# Mega_Shield.net
KiCad netlist of a schematic drawn in EAGLE
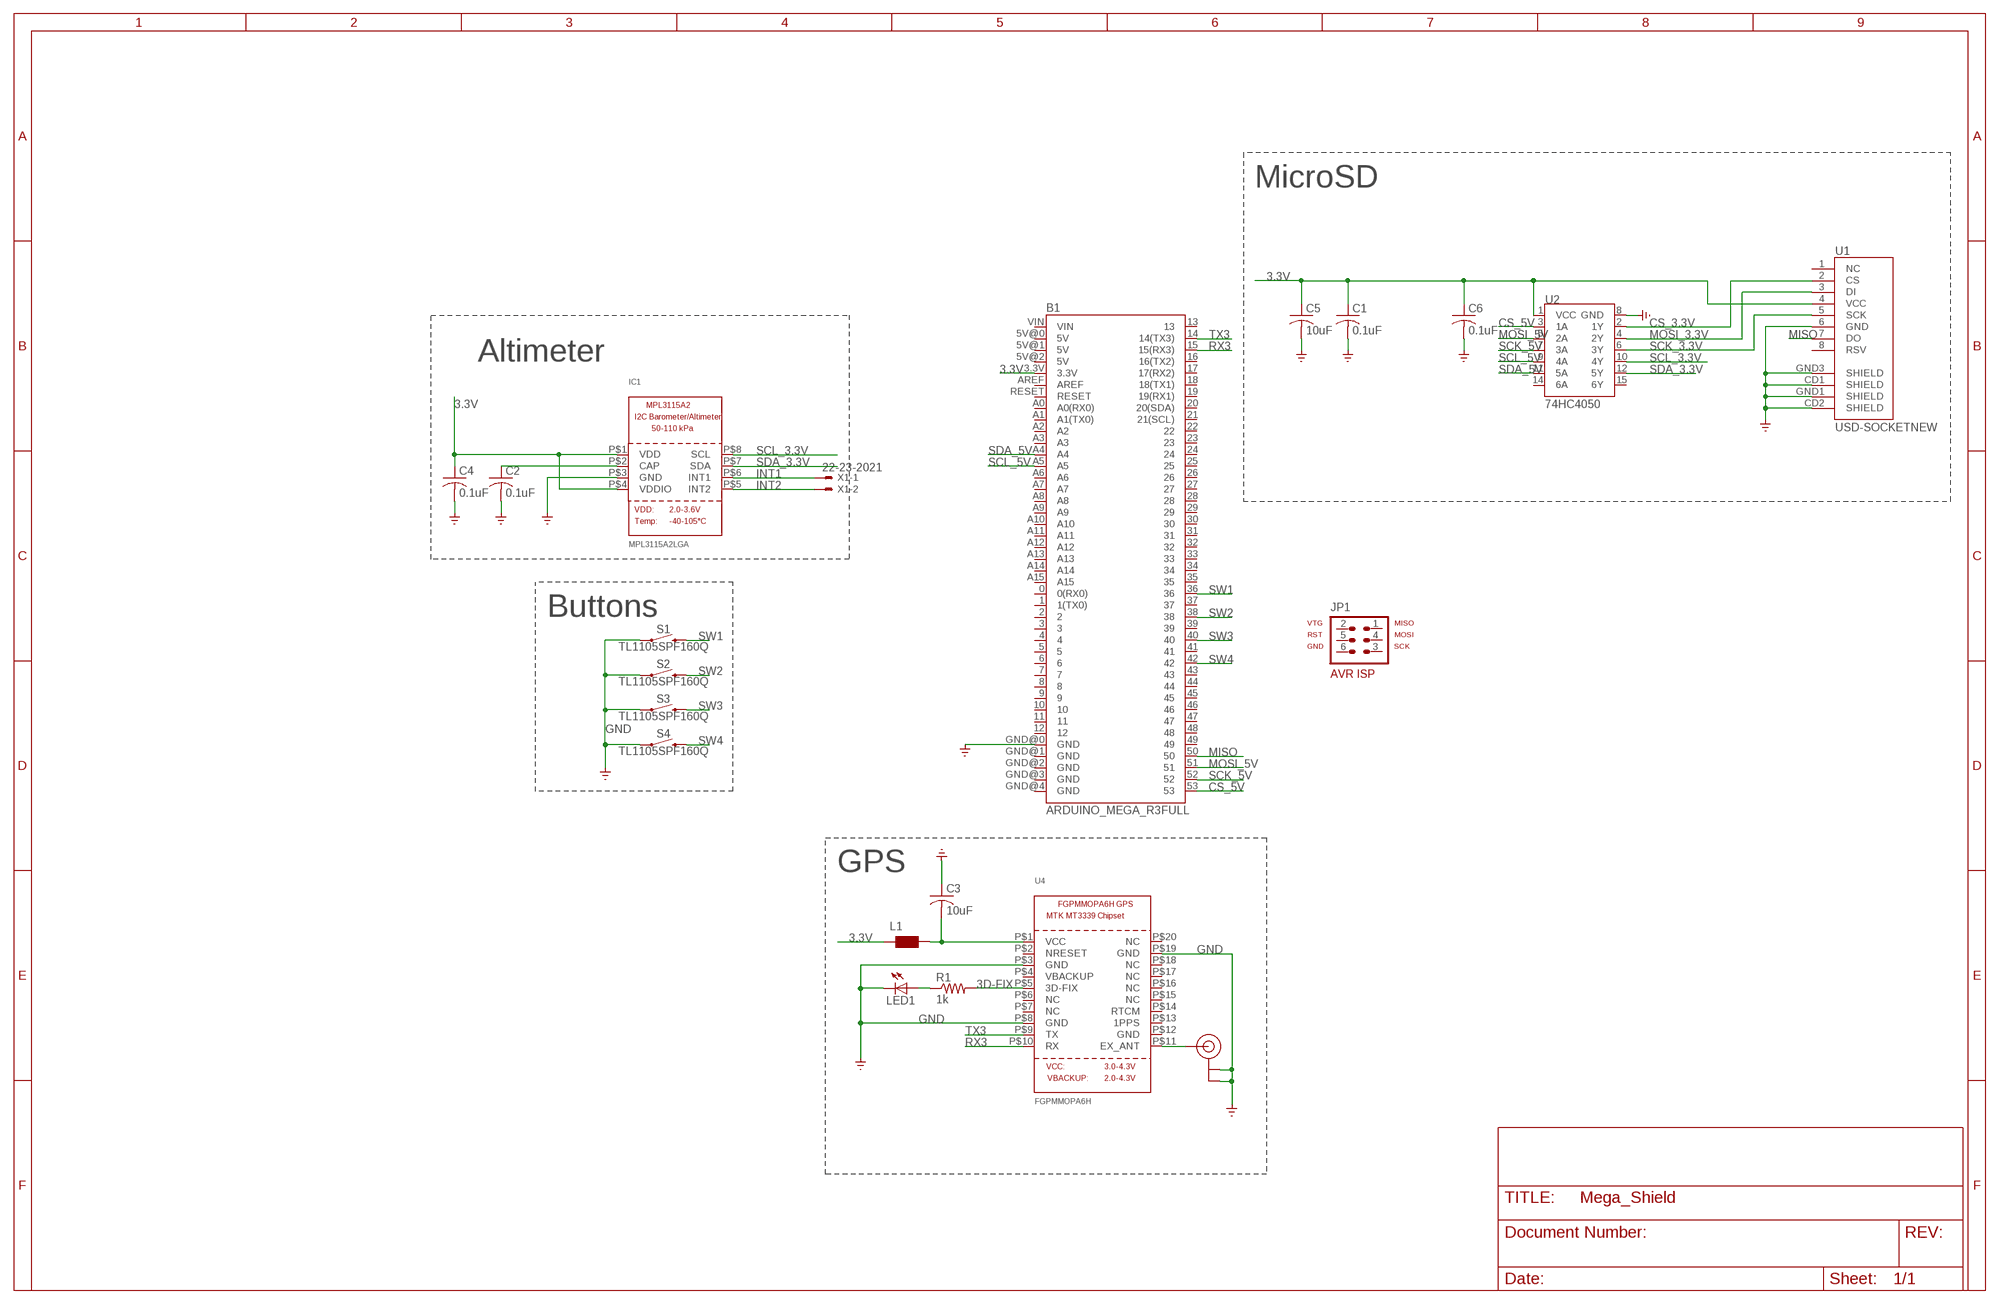
[diagram p0: schematic, sheet 1]

(export (version "E")
  (design (tool "Eeschema 10.0.6"))
  (components
    (comp (ref "B1")
      (value "ARDUINO_MEGA_R3FULL")
      (footprint "eagle-import:ARDUINO_MEGA")
      (libsource (lib "eagle-import") (part "ARDUINO_MEGA_R3FULL"))
    )
    (comp (ref "C1")
      (value "0.1uF")
      (footprint "eagle-import:C1206")
      (libsource (lib "eagle-import") (part "C-USC1206"))
    )
    (comp (ref "C2")
      (value "0.1uF")
      (footprint "eagle-import:C1206")
      (libsource (lib "eagle-import") (part "C-USC1206"))
    )
    (comp (ref "C3")
      (value "10uF")
      (footprint "eagle-import:C1206")
      (libsource (lib "eagle-import") (part "C-USC1206"))
    )
    (comp (ref "C4")
      (value "0.1uF")
      (footprint "eagle-import:C1206")
      (libsource (lib "eagle-import") (part "C-USC1206"))
    )
    (comp (ref "C5")
      (value "10uF")
      (footprint "eagle-import:C1206")
      (libsource (lib "eagle-import") (part "C-USC1206"))
    )
    (comp (ref "C6")
      (value "0.1uF")
      (footprint "eagle-import:C1206")
      (libsource (lib "eagle-import") (part "C-USC1206"))
    )
    (comp (ref "IC1")
      (value "MPL3115A2LGA")
      (footprint "eagle-import:LGA8")
      (libsource (lib "eagle-import") (part "MPL3115A2LGA"))
    )
    (comp (ref "JP1")
      (value "AVR-ISP-6")
      (footprint "eagle-import:AVR-ISP-6")
      (libsource (lib "eagle-import") (part "AVR-ISP-6"))
    )
    (comp (ref "L1")
      (value "WE-CBF_1206")
      (footprint "eagle-import:1206")
      (libsource (lib "eagle-import") (part "WE-CBF_1206"))
    )
    (comp (ref "LED1")
      (value "LEDSMT1206")
      (footprint "eagle-import:1206")
      (libsource (lib "eagle-import") (part "LEDSMT1206"))
    )
    (comp (ref "R1")
      (value "1k")
      (footprint "eagle-import:R1206")
      (libsource (lib "eagle-import") (part "R-US_R1206"))
    )
    (comp (ref "S1")
      (value "TL1105SPF160Q")
      (footprint "eagle-import:TACTILE_SWITCH_PTH_6.0MM")
      (libsource (lib "eagle-import") (part "MOMENTARY-SWITCH-SPST-PTH-6.0MM"))
    )
    (comp (ref "S2")
      (value "TL1105SPF160Q")
      (footprint "eagle-import:TACTILE_SWITCH_PTH_6.0MM")
      (libsource (lib "eagle-import") (part "MOMENTARY-SWITCH-SPST-PTH-6.0MM"))
    )
    (comp (ref "S3")
      (value "TL1105SPF160Q")
      (footprint "eagle-import:TACTILE_SWITCH_PTH_6.0MM")
      (libsource (lib "eagle-import") (part "MOMENTARY-SWITCH-SPST-PTH-6.0MM"))
    )
    (comp (ref "S4")
      (value "TL1105SPF160Q")
      (footprint "eagle-import:TACTILE_SWITCH_PTH_6.0MM")
      (libsource (lib "eagle-import") (part "MOMENTARY-SWITCH-SPST-PTH-6.0MM"))
    )
    (comp (ref "U$20")
      (value "U.FL")
      (footprint "eagle-import:U.FL")
      (libsource (lib "eagle-import") (part "U.FL"))
    )
    (comp (ref "U1")
      (value "USD-SOCKETNEW")
      (footprint "eagle-import:MICRO-SD-SOCKET-PP")
      (libsource (lib "eagle-import") (part "USD-SOCKETNEW"))
    )
    (comp (ref "U2")
      (value "74HC4050")
      (footprint "eagle-import:SO16")
      (libsource (lib "eagle-import") (part "HEX_CONVERTER"))
    )
    (comp (ref "U4")
      (value "FGPMMOPA6H")
      (footprint "eagle-import:FGPMMOPA6H")
      (libsource (lib "eagle-import") (part "GPS_FGPMMOPA6H"))
    )
    (comp (ref "X1")
      (value "22-23-2021")
      (footprint "eagle-import:22-23-2021")
      (fields (field (name "MF") "MOLEX"))
      (libsource (lib "eagle-import") (part "22-23-2021"))
    )
  )
  (nets
    (net (code "1") (name "/3.3V") (class "Default")
      (node (ref "B1") (pin "3.3V") (pinfunction "3.3V_3.3V") (pintype "bidirectional"))
      (node (ref "C1") (pin "1") (pinfunction "1_1") (pintype "passive"))
      (node (ref "C4") (pin "1") (pinfunction "1_1") (pintype "passive"))
      (node (ref "C5") (pin "1") (pinfunction "1_1") (pintype "passive"))
      (node (ref "C6") (pin "1") (pinfunction "1_1") (pintype "passive"))
      (node (ref "IC1") (pin "P$1") (pinfunction "VDD_P$1") (pintype "power_in"))
      (node (ref "IC1") (pin "P$4") (pinfunction "VDDIO_P$4") (pintype "power_in"))
      (node (ref "L1") (pin "1") (pinfunction "1_1") (pintype "passive"))
      (node (ref "U1") (pin "4") (pinfunction "VCC_4") (pintype "bidirectional"))
      (node (ref "U2") (pin "1") (pinfunction "VCC_1") (pintype "bidirectional"))
    )
    (net (code "2") (name "/3D-FIX") (class "Default")
      (node (ref "R1") (pin "2") (pinfunction "2_2") (pintype "passive"))
      (node (ref "U4") (pin "P$5") (pinfunction "3D-FIX_P$5") (pintype "bidirectional"))
    )
    (net (code "3") (name "/CS_3.3V") (class "Default")
      (node (ref "U1") (pin "2") (pinfunction "CS_2") (pintype "bidirectional"))
      (node (ref "U2") (pin "2") (pinfunction "1Y_2") (pintype "bidirectional"))
    )
    (net (code "4") (name "/CS_5V") (class "Default")
      (node (ref "B1") (pin "53") (pinfunction "53_53") (pintype "bidirectional"))
      (node (ref "U2") (pin "3") (pinfunction "1A_3") (pintype "bidirectional"))
    )
    (net (code "5") (name "/INT1") (class "Default")
      (node (ref "IC1") (pin "P$6") (pinfunction "INT1_P$6") (pintype "output"))
      (node (ref "X1") (pin "1") (pinfunction "S_1") (pintype "passive"))
    )
    (net (code "6") (name "/INT2") (class "Default")
      (node (ref "IC1") (pin "P$5") (pinfunction "INT2_P$5") (pintype "output"))
      (node (ref "X1") (pin "2") (pinfunction "S_2") (pintype "passive"))
    )
    (net (code "7") (name "/MISO") (class "Default")
      (node (ref "B1") (pin "50") (pinfunction "50_50") (pintype "bidirectional"))
      (node (ref "U1") (pin "7") (pinfunction "DO_7") (pintype "bidirectional"))
    )
    (net (code "8") (name "/MOSI_3.3V") (class "Default")
      (node (ref "U1") (pin "3") (pinfunction "DI_3") (pintype "bidirectional"))
      (node (ref "U2") (pin "4") (pinfunction "2Y_4") (pintype "bidirectional"))
    )
    (net (code "9") (name "/MOSI_5V") (class "Default")
      (node (ref "B1") (pin "51") (pinfunction "51_51") (pintype "bidirectional"))
      (node (ref "U2") (pin "5") (pinfunction "2A_5") (pintype "bidirectional"))
    )
    (net (code "10") (name "/RX3") (class "Default")
      (node (ref "B1") (pin "15") (pinfunction "15(RX3)_15") (pintype "bidirectional"))
      (node (ref "U4") (pin "P$10") (pinfunction "RX_P$10") (pintype "bidirectional"))
    )
    (net (code "11") (name "/SCK_3.3V") (class "Default")
      (node (ref "U1") (pin "5") (pinfunction "SCK_5") (pintype "bidirectional"))
      (node (ref "U2") (pin "6") (pinfunction "3Y_6") (pintype "bidirectional"))
    )
    (net (code "12") (name "/SCK_5V") (class "Default")
      (node (ref "B1") (pin "52") (pinfunction "52_52") (pintype "bidirectional"))
      (node (ref "U2") (pin "7") (pinfunction "3A_7") (pintype "bidirectional"))
    )
    (net (code "13") (name "/SCL_3.3V") (class "Default")
      (node (ref "IC1") (pin "P$8") (pinfunction "SCL_P$8") (pintype "bidirectional"))
      (node (ref "U2") (pin "10") (pinfunction "4Y_10") (pintype "bidirectional"))
    )
    (net (code "14") (name "/SCL_5V") (class "Default")
      (node (ref "B1") (pin "A5") (pinfunction "A5_A5") (pintype "bidirectional"))
      (node (ref "U2") (pin "9") (pinfunction "4A_9") (pintype "bidirectional"))
    )
    (net (code "15") (name "/SDA_3.3V") (class "Default")
      (node (ref "IC1") (pin "P$7") (pinfunction "SDA_P$7") (pintype "bidirectional"))
      (node (ref "U2") (pin "12") (pinfunction "5Y_12") (pintype "bidirectional"))
    )
    (net (code "16") (name "/SDA_5V") (class "Default")
      (node (ref "B1") (pin "A4") (pinfunction "A4_A4") (pintype "bidirectional"))
      (node (ref "U2") (pin "11") (pinfunction "5A_11") (pintype "bidirectional"))
    )
    (net (code "17") (name "/SW1") (class "Default")
      (node (ref "B1") (pin "36") (pinfunction "36_36") (pintype "bidirectional"))
      (node (ref "S1") (pin "3") (pinfunction "2_3") (pintype "passive"))
    )
    (net (code "18") (name "/SW2") (class "Default")
      (node (ref "B1") (pin "38") (pinfunction "38_38") (pintype "bidirectional"))
      (node (ref "S2") (pin "3") (pinfunction "2_3") (pintype "passive"))
    )
    (net (code "19") (name "/SW3") (class "Default")
      (node (ref "B1") (pin "40") (pinfunction "40_40") (pintype "bidirectional"))
      (node (ref "S3") (pin "3") (pinfunction "2_3") (pintype "passive"))
    )
    (net (code "20") (name "/SW4") (class "Default")
      (node (ref "B1") (pin "42") (pinfunction "42_42") (pintype "bidirectional"))
      (node (ref "S4") (pin "3") (pinfunction "2_3") (pintype "passive"))
    )
    (net (code "21") (name "/TX3") (class "Default")
      (node (ref "B1") (pin "14") (pinfunction "14(TX3)_14") (pintype "bidirectional"))
      (node (ref "U4") (pin "P$9") (pinfunction "TX_P$9") (pintype "bidirectional"))
    )
    (net (code "22") (name "GND_") (class "Default")
      (node (ref "B1") (pin "GND@0") (pinfunction "GND_GND@0") (pintype "bidirectional"))
      (node (ref "C1") (pin "2") (pinfunction "2_2") (pintype "passive"))
      (node (ref "C2") (pin "2") (pinfunction "2_2") (pintype "passive"))
      (node (ref "C3") (pin "1") (pinfunction "1_1") (pintype "passive"))
      (node (ref "C4") (pin "2") (pinfunction "2_2") (pintype "passive"))
      (node (ref "C5") (pin "2") (pinfunction "2_2") (pintype "passive"))
      (node (ref "C6") (pin "2") (pinfunction "2_2") (pintype "passive"))
      (node (ref "IC1") (pin "P$3") (pinfunction "GND_P$3") (pintype "power_in"))
      (node (ref "LED1") (pin "C") (pinfunction "C_C") (pintype "passive"))
      (node (ref "S1") (pin "1") (pinfunction "1_1") (pintype "passive"))
      (node (ref "S2") (pin "1") (pinfunction "1_1") (pintype "passive"))
      (node (ref "S3") (pin "1") (pinfunction "1_1") (pintype "passive"))
      (node (ref "S4") (pin "1") (pinfunction "1_1") (pintype "passive"))
      (node (ref "U$20") (pin "P$1") (pinfunction "GND_P$1") (pintype "bidirectional"))
      (node (ref "U$20") (pin "P$2") (pinfunction "GND_P$2") (pintype "bidirectional"))
      (node (ref "U1") (pin "6") (pinfunction "GND_6") (pintype "bidirectional"))
      (node (ref "U1") (pin "CD1") (pinfunction "SHIELD_CD1") (pintype "bidirectional"))
      (node (ref "U1") (pin "CD2") (pinfunction "SHIELD_CD2") (pintype "bidirectional"))
      (node (ref "U1") (pin "GND1") (pinfunction "SHIELD_GND1") (pintype "bidirectional"))
      (node (ref "U1") (pin "GND3") (pinfunction "SHIELD_GND3") (pintype "bidirectional"))
      (node (ref "U2") (pin "8") (pinfunction "GND_8") (pintype "bidirectional"))
      (node (ref "U4") (pin "P$19") (pinfunction "GND_P$19") (pintype "bidirectional"))
      (node (ref "U4") (pin "P$3") (pinfunction "GND_P$3") (pintype "bidirectional"))
      (node (ref "U4") (pin "P$8") (pinfunction "GND_P$8") (pintype "bidirectional"))
    )
    (net (code "23") (name "Net-(IC1-CAP)") (class "Default")
      (node (ref "C2") (pin "1") (pinfunction "1_1") (pintype "passive"))
      (node (ref "IC1") (pin "P$2") (pinfunction "CAP_P$2") (pintype "passive"))
    )
    (net (code "24") (name "Net-(LED1-PadA)") (class "Default")
      (node (ref "LED1") (pin "A") (pinfunction "A_A") (pintype "passive"))
      (node (ref "R1") (pin "1") (pinfunction "1_1") (pintype "passive"))
    )
    (net (code "25") (name "Net-(U$20-SIGNAL)") (class "Default")
      (node (ref "U$20") (pin "P$3") (pinfunction "SIGNAL_P$3") (pintype "bidirectional"))
      (node (ref "U4") (pin "P$11") (pinfunction "EX_ANT_P$11") (pintype "bidirectional"))
    )
    (net (code "26") (name "Net-(U4-VCC)") (class "Default")
      (node (ref "C3") (pin "2") (pinfunction "2_2") (pintype "passive"))
      (node (ref "L1") (pin "2") (pinfunction "2_2") (pintype "passive"))
      (node (ref "U4") (pin "P$1") (pinfunction "VCC_P$1") (pintype "bidirectional"))
    )
    (net (code "27") (name "unconnected-(B1-0(RX0)-Pad0)") (class "Default")
      (node (ref "B1") (pin "0") (pinfunction "0(RX0)_0") (pintype "bidirectional"))
    )
    (net (code "28") (name "unconnected-(B1-1(TX0)-Pad1)") (class "Default")
      (node (ref "B1") (pin "1") (pinfunction "1(TX0)_1") (pintype "bidirectional"))
    )
    (net (code "29") (name "unconnected-(B1-5V-Pad5V@0)") (class "Default")
      (node (ref "B1") (pin "5V@0") (pinfunction "5V_5V@0") (pintype "bidirectional"))
    )
    (net (code "30") (name "unconnected-(B1-5V-Pad5V@1)") (class "Default")
      (node (ref "B1") (pin "5V@1") (pinfunction "5V_5V@1") (pintype "bidirectional"))
    )
    (net (code "31") (name "unconnected-(B1-5V-Pad5V@2)") (class "Default")
      (node (ref "B1") (pin "5V@2") (pinfunction "5V_5V@2") (pintype "bidirectional"))
    )
    (net (code "32") (name "unconnected-(B1-16(TX2)-Pad16)") (class "Default")
      (node (ref "B1") (pin "16") (pinfunction "16(TX2)_16") (pintype "bidirectional"))
    )
    (net (code "33") (name "unconnected-(B1-17(RX2)-Pad17)") (class "Default")
      (node (ref "B1") (pin "17") (pinfunction "17(RX2)_17") (pintype "bidirectional"))
    )
    (net (code "34") (name "unconnected-(B1-18(TX1)-Pad18)") (class "Default")
      (node (ref "B1") (pin "18") (pinfunction "18(TX1)_18") (pintype "bidirectional"))
    )
    (net (code "35") (name "unconnected-(B1-19(RX1)-Pad19)") (class "Default")
      (node (ref "B1") (pin "19") (pinfunction "19(RX1)_19") (pintype "bidirectional"))
    )
    (net (code "36") (name "unconnected-(B1-20(SDA)-Pad20)") (class "Default")
      (node (ref "B1") (pin "20") (pinfunction "20(SDA)_20") (pintype "bidirectional"))
    )
    (net (code "37") (name "unconnected-(B1-21(SCL)-Pad21)") (class "Default")
      (node (ref "B1") (pin "21") (pinfunction "21(SCL)_21") (pintype "bidirectional"))
    )
    (net (code "38") (name "unconnected-(B1-A0(RX0)-PadA0)") (class "Default")
      (node (ref "B1") (pin "A0") (pinfunction "A0(RX0)_A0") (pintype "bidirectional"))
    )
    (net (code "39") (name "unconnected-(B1-A1(TX0)-PadA1)") (class "Default")
      (node (ref "B1") (pin "A1") (pinfunction "A1(TX0)_A1") (pintype "bidirectional"))
    )
    (net (code "40") (name "unconnected-(B1-GND-PadGND@1)") (class "Default")
      (node (ref "B1") (pin "GND@1") (pinfunction "GND_GND@1") (pintype "bidirectional"))
    )
    (net (code "41") (name "unconnected-(B1-GND-PadGND@2)") (class "Default")
      (node (ref "B1") (pin "GND@2") (pinfunction "GND_GND@2") (pintype "bidirectional"))
    )
    (net (code "42") (name "unconnected-(B1-GND-PadGND@3)") (class "Default")
      (node (ref "B1") (pin "GND@3") (pinfunction "GND_GND@3") (pintype "bidirectional"))
    )
    (net (code "43") (name "unconnected-(B1-GND-PadGND@4)") (class "Default")
      (node (ref "B1") (pin "GND@4") (pinfunction "GND_GND@4") (pintype "bidirectional"))
    )
    (net (code "44") (name "unconnected-(B1-Pad2)") (class "Default")
      (node (ref "B1") (pin "2") (pinfunction "2_2") (pintype "bidirectional"))
    )
    (net (code "45") (name "unconnected-(B1-Pad3)") (class "Default")
      (node (ref "B1") (pin "3") (pinfunction "3_3") (pintype "bidirectional"))
    )
    (net (code "46") (name "unconnected-(B1-Pad4)") (class "Default")
      (node (ref "B1") (pin "4") (pinfunction "4_4") (pintype "bidirectional"))
    )
    (net (code "47") (name "unconnected-(B1-Pad5)") (class "Default")
      (node (ref "B1") (pin "5") (pinfunction "5_5") (pintype "bidirectional"))
    )
    (net (code "48") (name "unconnected-(B1-Pad6)") (class "Default")
      (node (ref "B1") (pin "6") (pinfunction "6_6") (pintype "bidirectional"))
    )
    (net (code "49") (name "unconnected-(B1-Pad7)") (class "Default")
      (node (ref "B1") (pin "7") (pinfunction "7_7") (pintype "bidirectional"))
    )
    (net (code "50") (name "unconnected-(B1-Pad8)") (class "Default")
      (node (ref "B1") (pin "8") (pinfunction "8_8") (pintype "bidirectional"))
    )
    (net (code "51") (name "unconnected-(B1-Pad9)") (class "Default")
      (node (ref "B1") (pin "9") (pinfunction "9_9") (pintype "bidirectional"))
    )
    (net (code "52") (name "unconnected-(B1-Pad10)") (class "Default")
      (node (ref "B1") (pin "10") (pinfunction "10_10") (pintype "bidirectional"))
    )
    (net (code "53") (name "unconnected-(B1-Pad11)") (class "Default")
      (node (ref "B1") (pin "11") (pinfunction "11_11") (pintype "bidirectional"))
    )
    (net (code "54") (name "unconnected-(B1-Pad12)") (class "Default")
      (node (ref "B1") (pin "12") (pinfunction "12_12") (pintype "bidirectional"))
    )
    (net (code "55") (name "unconnected-(B1-Pad13)") (class "Default")
      (node (ref "B1") (pin "13") (pinfunction "13_13") (pintype "bidirectional"))
    )
    (net (code "56") (name "unconnected-(B1-Pad22)") (class "Default")
      (node (ref "B1") (pin "22") (pinfunction "22_22") (pintype "bidirectional"))
    )
    (net (code "57") (name "unconnected-(B1-Pad23)") (class "Default")
      (node (ref "B1") (pin "23") (pinfunction "23_23") (pintype "bidirectional"))
    )
    (net (code "58") (name "unconnected-(B1-Pad24)") (class "Default")
      (node (ref "B1") (pin "24") (pinfunction "24_24") (pintype "bidirectional"))
    )
    (net (code "59") (name "unconnected-(B1-Pad25)") (class "Default")
      (node (ref "B1") (pin "25") (pinfunction "25_25") (pintype "bidirectional"))
    )
    (net (code "60") (name "unconnected-(B1-Pad26)") (class "Default")
      (node (ref "B1") (pin "26") (pinfunction "26_26") (pintype "bidirectional"))
    )
    (net (code "61") (name "unconnected-(B1-Pad27)") (class "Default")
      (node (ref "B1") (pin "27") (pinfunction "27_27") (pintype "bidirectional"))
    )
    (net (code "62") (name "unconnected-(B1-Pad28)") (class "Default")
      (node (ref "B1") (pin "28") (pinfunction "28_28") (pintype "bidirectional"))
    )
    (net (code "63") (name "unconnected-(B1-Pad29)") (class "Default")
      (node (ref "B1") (pin "29") (pinfunction "29_29") (pintype "bidirectional"))
    )
    (net (code "64") (name "unconnected-(B1-Pad30)") (class "Default")
      (node (ref "B1") (pin "30") (pinfunction "30_30") (pintype "bidirectional"))
    )
    (net (code "65") (name "unconnected-(B1-Pad31)") (class "Default")
      (node (ref "B1") (pin "31") (pinfunction "31_31") (pintype "bidirectional"))
    )
    (net (code "66") (name "unconnected-(B1-Pad32)") (class "Default")
      (node (ref "B1") (pin "32") (pinfunction "32_32") (pintype "bidirectional"))
    )
    (net (code "67") (name "unconnected-(B1-Pad33)") (class "Default")
      (node (ref "B1") (pin "33") (pinfunction "33_33") (pintype "bidirectional"))
    )
    (net (code "68") (name "unconnected-(B1-Pad34)") (class "Default")
      (node (ref "B1") (pin "34") (pinfunction "34_34") (pintype "bidirectional"))
    )
    (net (code "69") (name "unconnected-(B1-Pad35)") (class "Default")
      (node (ref "B1") (pin "35") (pinfunction "35_35") (pintype "bidirectional"))
    )
    (net (code "70") (name "unconnected-(B1-Pad37)") (class "Default")
      (node (ref "B1") (pin "37") (pinfunction "37_37") (pintype "bidirectional"))
    )
    (net (code "71") (name "unconnected-(B1-Pad39)") (class "Default")
      (node (ref "B1") (pin "39") (pinfunction "39_39") (pintype "bidirectional"))
    )
    (net (code "72") (name "unconnected-(B1-Pad41)") (class "Default")
      (node (ref "B1") (pin "41") (pinfunction "41_41") (pintype "bidirectional"))
    )
    (net (code "73") (name "unconnected-(B1-Pad43)") (class "Default")
      (node (ref "B1") (pin "43") (pinfunction "43_43") (pintype "bidirectional"))
    )
    (net (code "74") (name "unconnected-(B1-Pad44)") (class "Default")
      (node (ref "B1") (pin "44") (pinfunction "44_44") (pintype "bidirectional"))
    )
    (net (code "75") (name "unconnected-(B1-Pad45)") (class "Default")
      (node (ref "B1") (pin "45") (pinfunction "45_45") (pintype "bidirectional"))
    )
    (net (code "76") (name "unconnected-(B1-Pad46)") (class "Default")
      (node (ref "B1") (pin "46") (pinfunction "46_46") (pintype "bidirectional"))
    )
    (net (code "77") (name "unconnected-(B1-Pad47)") (class "Default")
      (node (ref "B1") (pin "47") (pinfunction "47_47") (pintype "bidirectional"))
    )
    (net (code "78") (name "unconnected-(B1-Pad48)") (class "Default")
      (node (ref "B1") (pin "48") (pinfunction "48_48") (pintype "bidirectional"))
    )
    (net (code "79") (name "unconnected-(B1-Pad49)") (class "Default")
      (node (ref "B1") (pin "49") (pinfunction "49_49") (pintype "bidirectional"))
    )
    (net (code "80") (name "unconnected-(B1-PadA2)") (class "Default")
      (node (ref "B1") (pin "A2") (pinfunction "A2_A2") (pintype "bidirectional"))
    )
    (net (code "81") (name "unconnected-(B1-PadA3)") (class "Default")
      (node (ref "B1") (pin "A3") (pinfunction "A3_A3") (pintype "bidirectional"))
    )
    (net (code "82") (name "unconnected-(B1-PadA6)") (class "Default")
      (node (ref "B1") (pin "A6") (pinfunction "A6_A6") (pintype "bidirectional"))
    )
    (net (code "83") (name "unconnected-(B1-PadA7)") (class "Default")
      (node (ref "B1") (pin "A7") (pinfunction "A7_A7") (pintype "bidirectional"))
    )
    (net (code "84") (name "unconnected-(B1-PadA8)") (class "Default")
      (node (ref "B1") (pin "A8") (pinfunction "A8_A8") (pintype "bidirectional"))
    )
    (net (code "85") (name "unconnected-(B1-PadA9)") (class "Default")
      (node (ref "B1") (pin "A9") (pinfunction "A9_A9") (pintype "bidirectional"))
    )
    (net (code "86") (name "unconnected-(B1-PadA10)") (class "Default")
      (node (ref "B1") (pin "A10") (pinfunction "A10_A10") (pintype "bidirectional"))
    )
    (net (code "87") (name "unconnected-(B1-PadA11)") (class "Default")
      (node (ref "B1") (pin "A11") (pinfunction "A11_A11") (pintype "bidirectional"))
    )
    (net (code "88") (name "unconnected-(B1-PadA12)") (class "Default")
      (node (ref "B1") (pin "A12") (pinfunction "A12_A12") (pintype "bidirectional"))
    )
    (net (code "89") (name "unconnected-(B1-PadA13)") (class "Default")
      (node (ref "B1") (pin "A13") (pinfunction "A13_A13") (pintype "bidirectional"))
    )
    (net (code "90") (name "unconnected-(B1-PadA14)") (class "Default")
      (node (ref "B1") (pin "A14") (pinfunction "A14_A14") (pintype "bidirectional"))
    )
    (net (code "91") (name "unconnected-(B1-PadA15)") (class "Default")
      (node (ref "B1") (pin "A15") (pinfunction "A15_A15") (pintype "bidirectional"))
    )
    (net (code "92") (name "unconnected-(B1-PadAREF)") (class "Default")
      (node (ref "B1") (pin "AREF") (pinfunction "AREF_AREF") (pintype "bidirectional"))
    )
    (net (code "93") (name "unconnected-(B1-PadRESET)") (class "Default")
      (node (ref "B1") (pin "RESET") (pinfunction "RESET_RESET") (pintype "bidirectional"))
    )
    (net (code "94") (name "unconnected-(B1-PadVIN)") (class "Default")
      (node (ref "B1") (pin "VIN") (pinfunction "VIN_VIN") (pintype "bidirectional"))
    )
    (net (code "95") (name "unconnected-(JP1-Pad1)") (class "Default")
      (node (ref "JP1") (pin "1") (pinfunction "1_1") (pintype "passive"))
    )
    (net (code "96") (name "unconnected-(JP1-Pad2)") (class "Default")
      (node (ref "JP1") (pin "2") (pinfunction "2_2") (pintype "passive"))
    )
    (net (code "97") (name "unconnected-(JP1-Pad3)") (class "Default")
      (node (ref "JP1") (pin "3") (pinfunction "3_3") (pintype "passive"))
    )
    (net (code "98") (name "unconnected-(JP1-Pad4)") (class "Default")
      (node (ref "JP1") (pin "4") (pinfunction "4_4") (pintype "passive"))
    )
    (net (code "99") (name "unconnected-(JP1-Pad5)") (class "Default")
      (node (ref "JP1") (pin "5") (pinfunction "5_5") (pintype "passive"))
    )
    (net (code "100") (name "unconnected-(JP1-Pad6)") (class "Default")
      (node (ref "JP1") (pin "6") (pinfunction "6_6") (pintype "passive"))
    )
    (net (code "101") (name "unconnected-(U1-NC-Pad1)") (class "Default")
      (node (ref "U1") (pin "1") (pinfunction "NC_1") (pintype "bidirectional"))
    )
    (net (code "102") (name "unconnected-(U1-RSV-Pad8)") (class "Default")
      (node (ref "U1") (pin "8") (pinfunction "RSV_8") (pintype "bidirectional"))
    )
    (net (code "103") (name "unconnected-(U2-6A-Pad14)") (class "Default")
      (node (ref "U2") (pin "14") (pinfunction "6A_14") (pintype "bidirectional"))
    )
    (net (code "104") (name "unconnected-(U2-6Y-Pad15)") (class "Default")
      (node (ref "U2") (pin "15") (pinfunction "6Y_15") (pintype "bidirectional"))
    )
    (net (code "105") (name "unconnected-(U4-1PPS-PadP$13)") (class "Default")
      (node (ref "U4") (pin "P$13") (pinfunction "1PPS_P$13") (pintype "bidirectional"))
    )
    (net (code "106") (name "unconnected-(U4-GND-PadP$12)") (class "Default")
      (node (ref "U4") (pin "P$12") (pinfunction "GND_P$12") (pintype "bidirectional"))
    )
    (net (code "107") (name "unconnected-(U4-NC-PadP$6)") (class "Default")
      (node (ref "U4") (pin "P$6") (pinfunction "NC_P$6") (pintype "bidirectional"))
    )
    (net (code "108") (name "unconnected-(U4-NC-PadP$7)") (class "Default")
      (node (ref "U4") (pin "P$7") (pinfunction "NC_P$7") (pintype "bidirectional"))
    )
    (net (code "109") (name "unconnected-(U4-NC-PadP$15)") (class "Default")
      (node (ref "U4") (pin "P$15") (pinfunction "NC_P$15") (pintype "bidirectional"))
    )
    (net (code "110") (name "unconnected-(U4-NC-PadP$16)") (class "Default")
      (node (ref "U4") (pin "P$16") (pinfunction "NC_P$16") (pintype "bidirectional"))
    )
    (net (code "111") (name "unconnected-(U4-NC-PadP$17)") (class "Default")
      (node (ref "U4") (pin "P$17") (pinfunction "NC_P$17") (pintype "bidirectional"))
    )
    (net (code "112") (name "unconnected-(U4-NC-PadP$18)") (class "Default")
      (node (ref "U4") (pin "P$18") (pinfunction "NC_P$18") (pintype "bidirectional"))
    )
    (net (code "113") (name "unconnected-(U4-NC-PadP$20)") (class "Default")
      (node (ref "U4") (pin "P$20") (pinfunction "NC_P$20") (pintype "bidirectional"))
    )
    (net (code "114") (name "unconnected-(U4-NRESET-PadP$2)") (class "Default")
      (node (ref "U4") (pin "P$2") (pinfunction "NRESET_P$2") (pintype "bidirectional"))
    )
    (net (code "115") (name "unconnected-(U4-RTCM-PadP$14)") (class "Default")
      (node (ref "U4") (pin "P$14") (pinfunction "RTCM_P$14") (pintype "bidirectional"))
    )
    (net (code "116") (name "unconnected-(U4-VBACKUP-PadP$4)") (class "Default")
      (node (ref "U4") (pin "P$4") (pinfunction "VBACKUP_P$4") (pintype "bidirectional"))
    )
  )
)
